# nRF_board.net
KiCad netlist of a schematic drawn in EAGLE
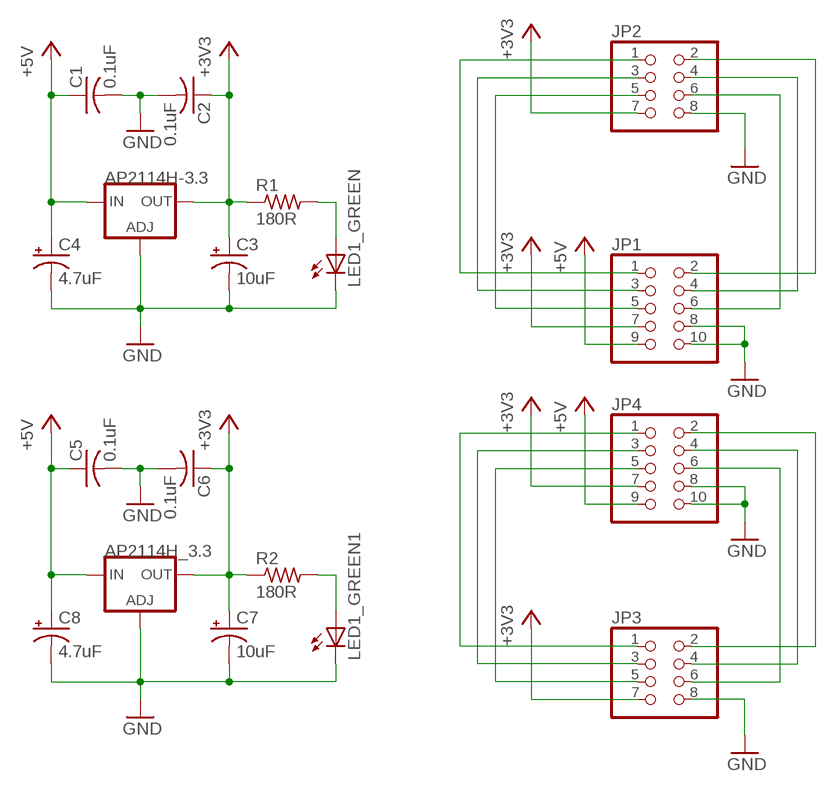
[diagram p0: schematic, sheet 1]

(export (version "E")
  (design (tool "Eeschema 10.0.6"))
  (components
    (comp (ref "AP2114H-3.3")
      (value "LD117AS28TR")
      (footprint "eagle-import:SOT223")
      (libsource (lib "eagle-import") (part "LD117A?S28TR"))
    )
    (comp (ref "AP2114H_3.3")
      (value "LD117AS28TR")
      (footprint "eagle-import:SOT223")
      (libsource (lib "eagle-import") (part "LD117A?S28TR"))
    )
    (comp (ref "C1")
      (value "0.1uF")
      (footprint "eagle-import:C1206K")
      (libsource (lib "eagle-import") (part "C-USC1206K"))
    )
    (comp (ref "C2")
      (value "0.1uF")
      (footprint "eagle-import:C1206K")
      (libsource (lib "eagle-import") (part "C-USC1206K"))
    )
    (comp (ref "C3")
      (value "10uF")
      (footprint "eagle-import:E2-5")
      (libsource (lib "eagle-import") (part "CPOL-USE2-5"))
    )
    (comp (ref "C4")
      (value "4.7uF")
      (footprint "eagle-import:E2-5")
      (libsource (lib "eagle-import") (part "CPOL-USE2-5"))
    )
    (comp (ref "C5")
      (value "0.1uF")
      (footprint "eagle-import:C1206K")
      (libsource (lib "eagle-import") (part "C-USC1206K"))
    )
    (comp (ref "C6")
      (value "0.1uF")
      (footprint "eagle-import:C1206K")
      (libsource (lib "eagle-import") (part "C-USC1206K"))
    )
    (comp (ref "C7")
      (value "10uF")
      (footprint "eagle-import:E2-5")
      (libsource (lib "eagle-import") (part "CPOL-USE2-5"))
    )
    (comp (ref "C8")
      (value "4.7uF")
      (footprint "eagle-import:E2-5")
      (libsource (lib "eagle-import") (part "CPOL-USE2-5"))
    )
    (comp (ref "JP1")
      (value "PINHD-2X5")
      (footprint "eagle-import:2X05")
      (libsource (lib "eagle-import") (part "PINHD-2X5"))
    )
    (comp (ref "JP2")
      (value "PINHD-2X4")
      (footprint "eagle-import:2X04")
      (libsource (lib "eagle-import") (part "PINHD-2X4"))
    )
    (comp (ref "JP3")
      (value "PINHD-2X4")
      (footprint "eagle-import:2X04")
      (libsource (lib "eagle-import") (part "PINHD-2X4"))
    )
    (comp (ref "JP4")
      (value "PINHD-2X5")
      (footprint "eagle-import:2X05")
      (libsource (lib "eagle-import") (part "PINHD-2X5"))
    )
    (comp (ref "LED1_GREEN")
      (value "LEDSMT1206")
      (footprint "eagle-import:1206")
      (libsource (lib "eagle-import") (part "LEDSMT1206"))
    )
    (comp (ref "LED1_GREEN1")
      (value "LEDSMT1206")
      (footprint "eagle-import:1206")
      (libsource (lib "eagle-import") (part "LEDSMT1206"))
    )
    (comp (ref "R1")
      (value "180R")
      (footprint "eagle-import:R1206")
      (libsource (lib "eagle-import") (part "R-US_R1206"))
    )
    (comp (ref "R2")
      (value "180R")
      (footprint "eagle-import:R1206")
      (libsource (lib "eagle-import") (part "R-US_R1206"))
    )
  )
  (nets
    (net (code "1") (name "+3V3") (class "Default")
      (node (ref "AP2114H-3.3") (pin "4") (pinfunction "OUT_4") (pintype "passive"))
      (node (ref "AP2114H_3.3") (pin "4") (pinfunction "OUT_4") (pintype "passive"))
      (node (ref "C2") (pin "1") (pinfunction "1_1") (pintype "passive"))
      (node (ref "C3") (pin "+") (pinfunction "+_+") (pintype "passive"))
      (node (ref "C6") (pin "1") (pinfunction "1_1") (pintype "passive"))
      (node (ref "C7") (pin "+") (pinfunction "+_+") (pintype "passive"))
      (node (ref "JP1") (pin "7") (pinfunction "7_7") (pintype "passive"))
      (node (ref "JP2") (pin "7") (pinfunction "7_7") (pintype "passive"))
      (node (ref "JP3") (pin "7") (pinfunction "7_7") (pintype "passive"))
      (node (ref "JP4") (pin "7") (pinfunction "7_7") (pintype "passive"))
      (node (ref "R1") (pin "1") (pinfunction "1_1") (pintype "passive"))
      (node (ref "R2") (pin "1") (pinfunction "1_1") (pintype "passive"))
    )
    (net (code "2") (name "+5V") (class "Default")
      (node (ref "AP2114H-3.3") (pin "3") (pinfunction "IN_3") (pintype "input"))
      (node (ref "AP2114H_3.3") (pin "3") (pinfunction "IN_3") (pintype "input"))
      (node (ref "C1") (pin "1") (pinfunction "1_1") (pintype "passive"))
      (node (ref "C4") (pin "+") (pinfunction "+_+") (pintype "passive"))
      (node (ref "C5") (pin "1") (pinfunction "1_1") (pintype "passive"))
      (node (ref "C8") (pin "+") (pinfunction "+_+") (pintype "passive"))
      (node (ref "JP1") (pin "9") (pinfunction "9_9") (pintype "passive"))
      (node (ref "JP4") (pin "9") (pinfunction "9_9") (pintype "passive"))
    )
    (net (code "3") (name "GND") (class "Default")
      (node (ref "AP2114H-3.3") (pin "1") (pinfunction "ADJ_1") (pintype "input"))
      (node (ref "AP2114H_3.3") (pin "1") (pinfunction "ADJ_1") (pintype "input"))
      (node (ref "C1") (pin "2") (pinfunction "2_2") (pintype "passive"))
      (node (ref "C2") (pin "2") (pinfunction "2_2") (pintype "passive"))
      (node (ref "C3") (pin "-") (pinfunction "-_-") (pintype "passive"))
      (node (ref "C4") (pin "-") (pinfunction "-_-") (pintype "passive"))
      (node (ref "C5") (pin "2") (pinfunction "2_2") (pintype "passive"))
      (node (ref "C6") (pin "2") (pinfunction "2_2") (pintype "passive"))
      (node (ref "C7") (pin "-") (pinfunction "-_-") (pintype "passive"))
      (node (ref "C8") (pin "-") (pinfunction "-_-") (pintype "passive"))
      (node (ref "JP1") (pin "10") (pinfunction "10_10") (pintype "passive"))
      (node (ref "JP1") (pin "8") (pinfunction "8_8") (pintype "passive"))
      (node (ref "JP2") (pin "8") (pinfunction "8_8") (pintype "passive"))
      (node (ref "JP3") (pin "8") (pinfunction "8_8") (pintype "passive"))
      (node (ref "JP4") (pin "10") (pinfunction "10_10") (pintype "passive"))
      (node (ref "JP4") (pin "8") (pinfunction "8_8") (pintype "passive"))
      (node (ref "LED1_GREEN") (pin "C") (pinfunction "C_C") (pintype "passive"))
      (node (ref "LED1_GREEN1") (pin "C") (pinfunction "C_C") (pintype "passive"))
    )
    (net (code "4") (name "Net-(JP1-Pad1)") (class "Default")
      (node (ref "JP1") (pin "1") (pinfunction "1_1") (pintype "passive"))
      (node (ref "JP2") (pin "1") (pinfunction "1_1") (pintype "passive"))
    )
    (net (code "5") (name "Net-(JP1-Pad2)") (class "Default")
      (node (ref "JP1") (pin "2") (pinfunction "2_2") (pintype "passive"))
      (node (ref "JP2") (pin "2") (pinfunction "2_2") (pintype "passive"))
    )
    (net (code "6") (name "Net-(JP1-Pad3)") (class "Default")
      (node (ref "JP1") (pin "3") (pinfunction "3_3") (pintype "passive"))
      (node (ref "JP2") (pin "3") (pinfunction "3_3") (pintype "passive"))
    )
    (net (code "7") (name "Net-(JP1-Pad4)") (class "Default")
      (node (ref "JP1") (pin "4") (pinfunction "4_4") (pintype "passive"))
      (node (ref "JP2") (pin "4") (pinfunction "4_4") (pintype "passive"))
    )
    (net (code "8") (name "Net-(JP1-Pad5)") (class "Default")
      (node (ref "JP1") (pin "5") (pinfunction "5_5") (pintype "passive"))
      (node (ref "JP2") (pin "5") (pinfunction "5_5") (pintype "passive"))
    )
    (net (code "9") (name "Net-(JP1-Pad6)") (class "Default")
      (node (ref "JP1") (pin "6") (pinfunction "6_6") (pintype "passive"))
      (node (ref "JP2") (pin "6") (pinfunction "6_6") (pintype "passive"))
    )
    (net (code "10") (name "Net-(JP3-Pad1)") (class "Default")
      (node (ref "JP3") (pin "1") (pinfunction "1_1") (pintype "passive"))
      (node (ref "JP4") (pin "1") (pinfunction "1_1") (pintype "passive"))
    )
    (net (code "11") (name "Net-(JP3-Pad2)") (class "Default")
      (node (ref "JP3") (pin "2") (pinfunction "2_2") (pintype "passive"))
      (node (ref "JP4") (pin "2") (pinfunction "2_2") (pintype "passive"))
    )
    (net (code "12") (name "Net-(JP3-Pad3)") (class "Default")
      (node (ref "JP3") (pin "3") (pinfunction "3_3") (pintype "passive"))
      (node (ref "JP4") (pin "3") (pinfunction "3_3") (pintype "passive"))
    )
    (net (code "13") (name "Net-(JP3-Pad4)") (class "Default")
      (node (ref "JP3") (pin "4") (pinfunction "4_4") (pintype "passive"))
      (node (ref "JP4") (pin "4") (pinfunction "4_4") (pintype "passive"))
    )
    (net (code "14") (name "Net-(JP3-Pad5)") (class "Default")
      (node (ref "JP3") (pin "5") (pinfunction "5_5") (pintype "passive"))
      (node (ref "JP4") (pin "5") (pinfunction "5_5") (pintype "passive"))
    )
    (net (code "15") (name "Net-(JP3-Pad6)") (class "Default")
      (node (ref "JP3") (pin "6") (pinfunction "6_6") (pintype "passive"))
      (node (ref "JP4") (pin "6") (pinfunction "6_6") (pintype "passive"))
    )
    (net (code "16") (name "Net-(LED1_GREEN-PadA)") (class "Default")
      (node (ref "LED1_GREEN") (pin "A") (pinfunction "A_A") (pintype "passive"))
      (node (ref "R1") (pin "2") (pinfunction "2_2") (pintype "passive"))
    )
    (net (code "17") (name "Net-(LED1_GREEN1-PadA)") (class "Default")
      (node (ref "LED1_GREEN1") (pin "A") (pinfunction "A_A") (pintype "passive"))
      (node (ref "R2") (pin "2") (pinfunction "2_2") (pintype "passive"))
    )
  )
)
